# SpaceFleaSolar.net
KiCad netlist of a schematic drawn in EAGLE
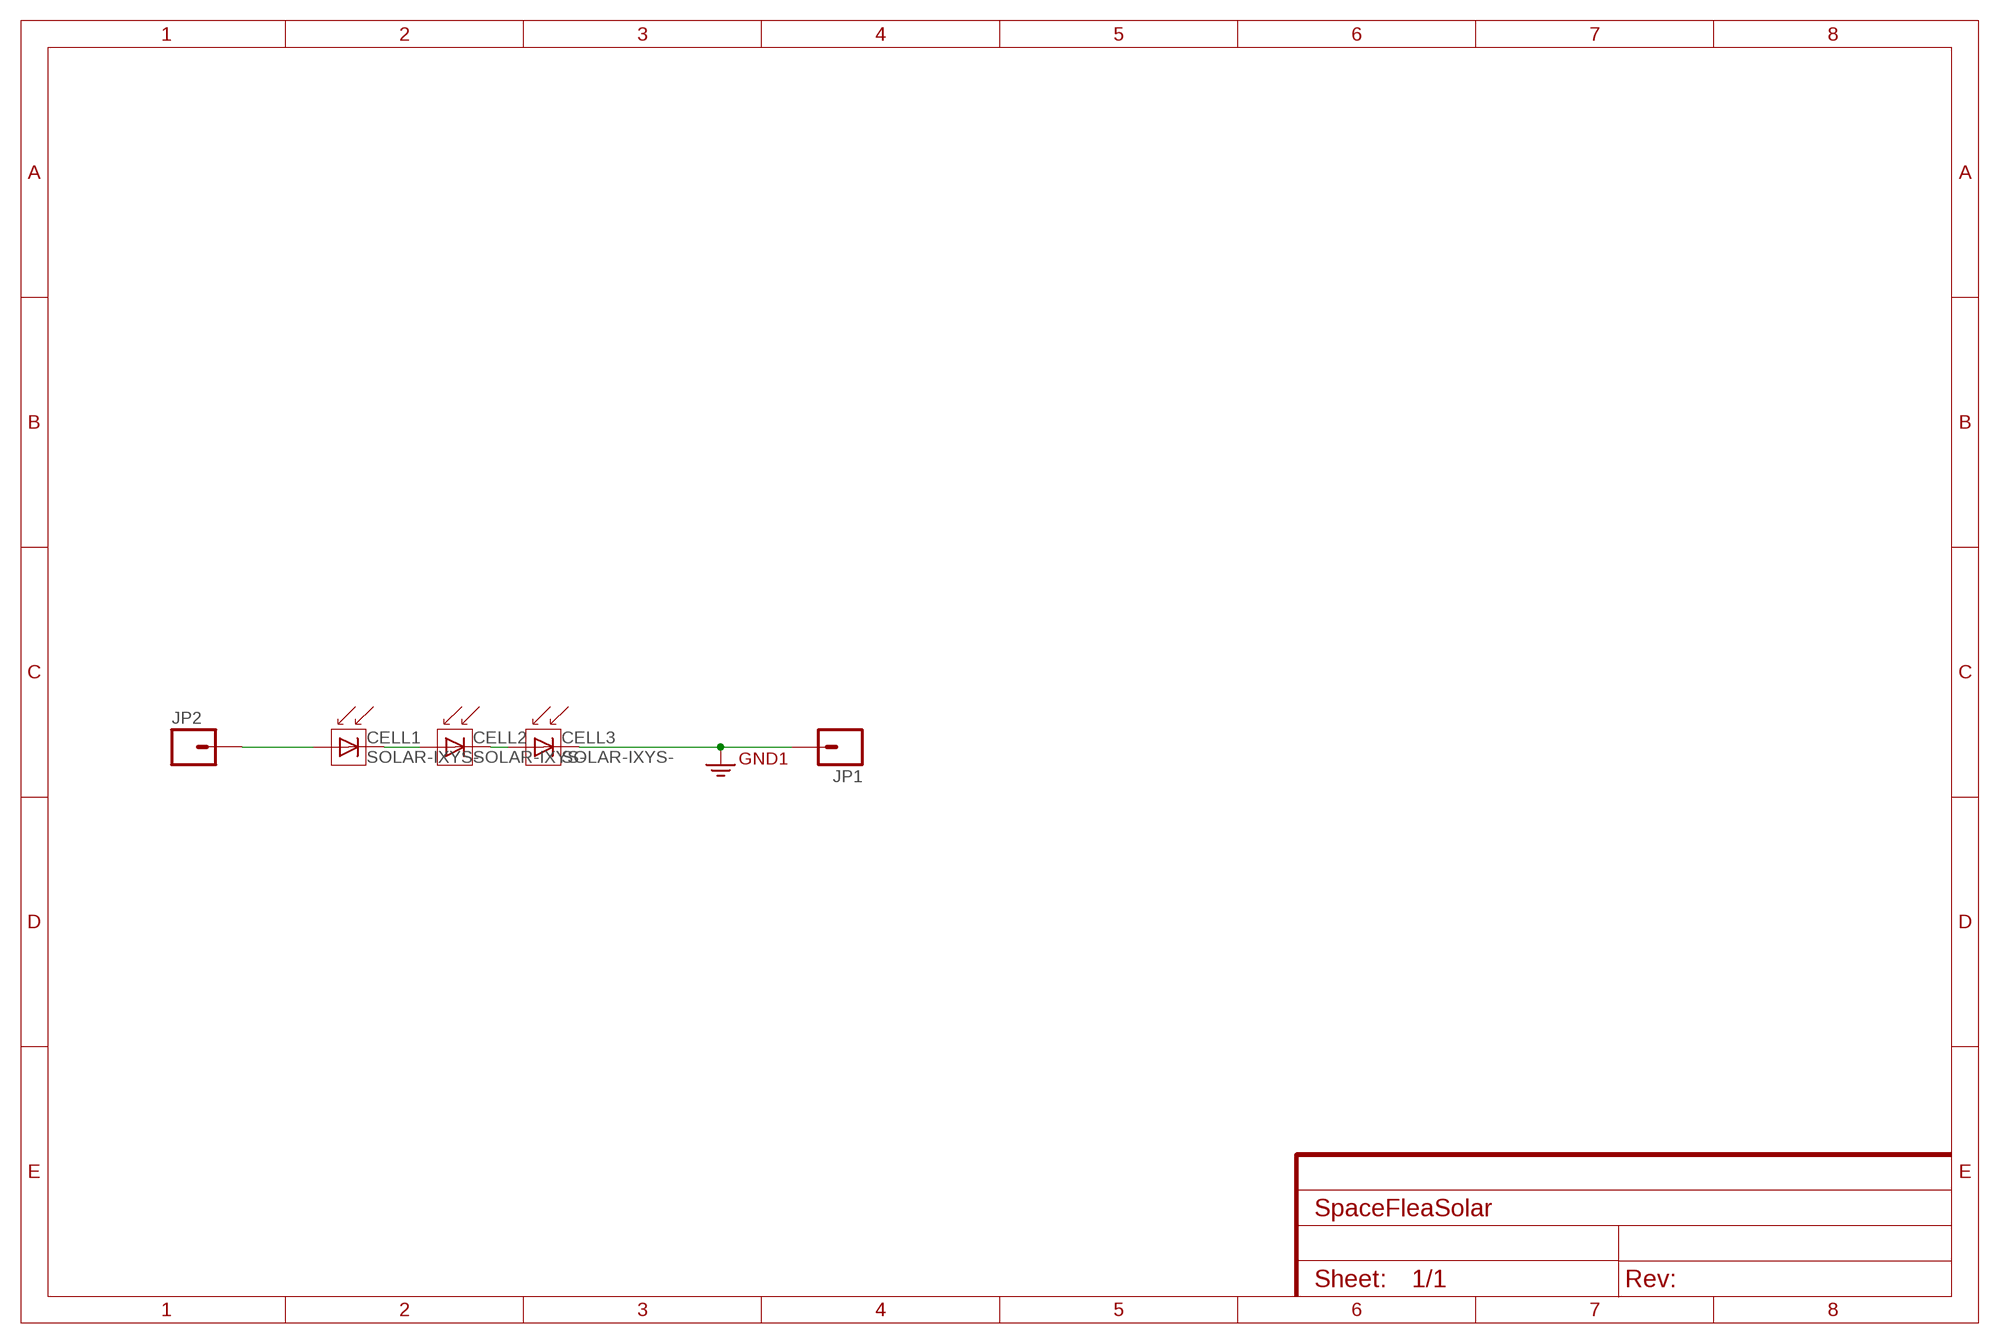
[diagram p0: schematic, sheet 1]

(export (version "E")
  (design (tool "Eeschema 10.0.6"))
  (components
    (comp (ref "CELL1")
      (value "SOLAR-IXYS-")
      (footprint "eagle-import:SOLARBIT-12X1")
      (libsource (lib "eagle-import") (part "SOLAR-IXYS-"))
    )
    (comp (ref "CELL2")
      (value "SOLAR-IXYS-")
      (footprint "eagle-import:SOLARBIT-12X1")
      (libsource (lib "eagle-import") (part "SOLAR-IXYS-"))
    )
    (comp (ref "CELL3")
      (value "SOLAR-IXYS-")
      (footprint "eagle-import:SOLARBIT-12X1")
      (libsource (lib "eagle-import") (part "SOLAR-IXYS-"))
    )
    (comp (ref "JP1")
      (value "M01PTH_2MM")
      (footprint "eagle-import:1X01_2MM")
      (libsource (lib "eagle-import") (part "M01PTH_2MM"))
    )
    (comp (ref "JP2")
      (value "M01PTH_2MM")
      (footprint "eagle-import:1X01_2MM")
      (libsource (lib "eagle-import") (part "M01PTH_2MM"))
    )
  )
  (nets
    (net (code "1") (name "GND2") (class "Default")
      (node (ref "CELL3") (pin "-") (pinfunction "C_-") (pintype "passive"))
      (node (ref "JP1") (pin "1") (pinfunction "1_1") (pintype "passive"))
    )
    (net (code "2") (name "Net-(CELL1-A)") (class "Default")
      (node (ref "CELL1") (pin "+") (pinfunction "A_+") (pintype "passive"))
      (node (ref "JP2") (pin "1") (pinfunction "1_1") (pintype "passive"))
    )
    (net (code "3") (name "Net-(CELL1-C)") (class "Default")
      (node (ref "CELL1") (pin "-") (pinfunction "C_-") (pintype "passive"))
      (node (ref "CELL2") (pin "+") (pinfunction "A_+") (pintype "passive"))
    )
    (net (code "4") (name "Net-(CELL2-C)") (class "Default")
      (node (ref "CELL2") (pin "-") (pinfunction "C_-") (pintype "passive"))
      (node (ref "CELL3") (pin "+") (pinfunction "A_+") (pintype "passive"))
    )
  )
)
